# Plata2.net
KiCad netlist of a schematic drawn in EAGLE
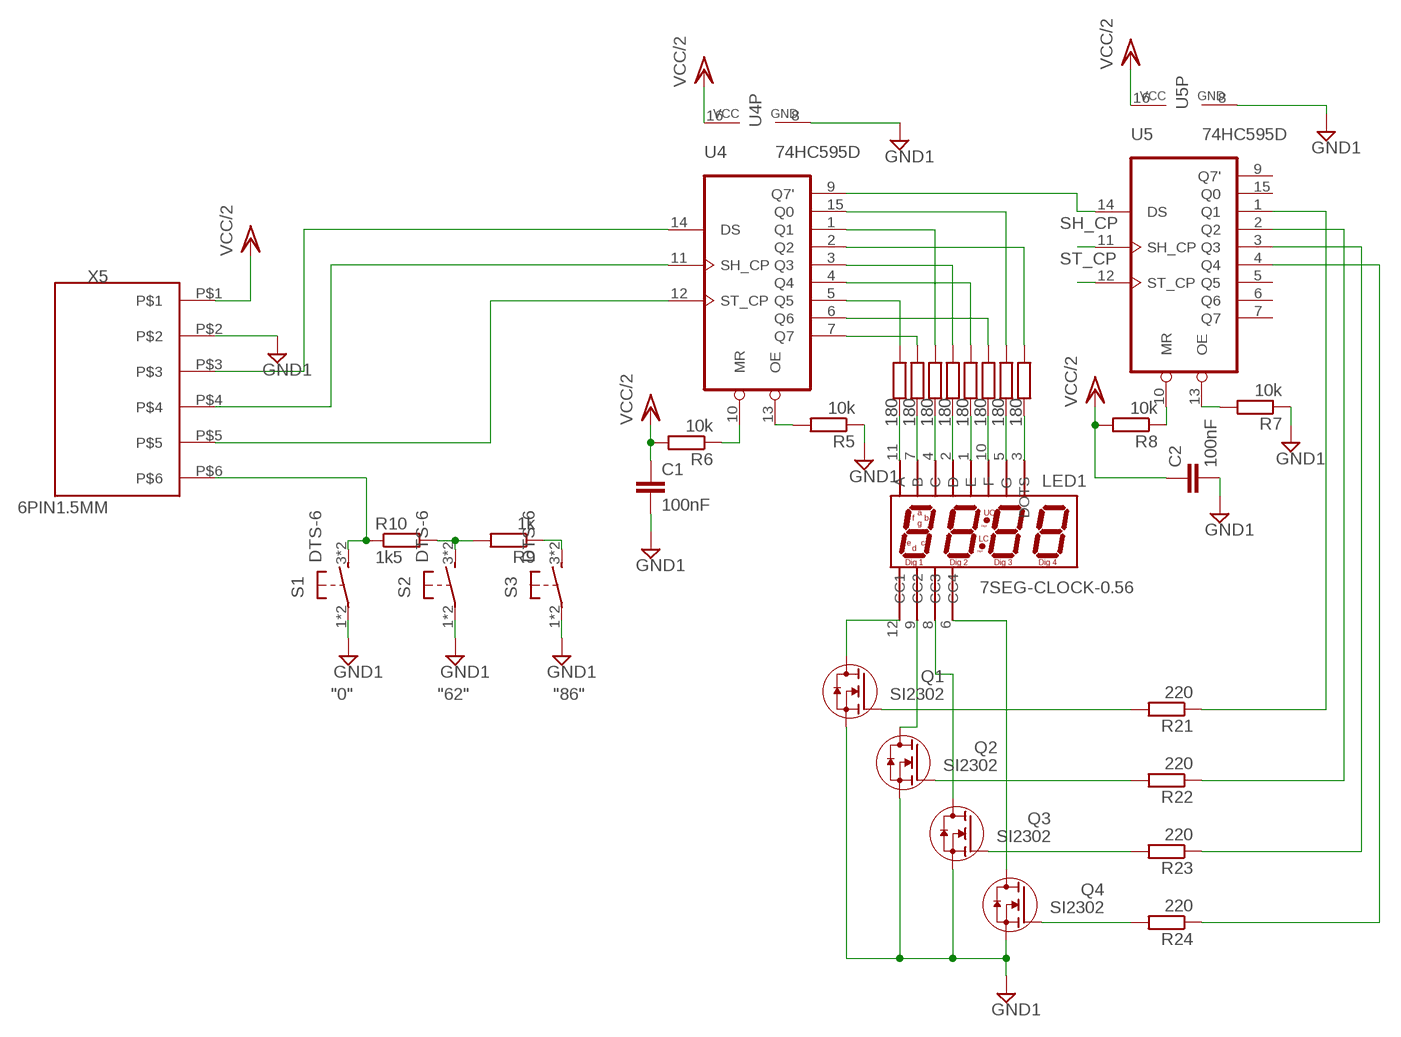
[diagram p0: schematic, sheet 1]

(export (version "E")
  (design (tool "Eeschema 10.0.6"))
  (components
    (comp (ref "C1")
      (value "100nF")
      (footprint "eagle-import:C0603")
      (libsource (lib "eagle-import") (part "C-EUC0603"))
    )
    (comp (ref "C2")
      (value "100nF")
      (footprint "eagle-import:C0603")
      (libsource (lib "eagle-import") (part "C-EUC0603"))
    )
    (comp (ref "LED1")
      (value "7SEG-CLOCK-0.56")
      (footprint "eagle-import:7SEG_4DIG_0.56")
      (libsource (lib "eagle-import") (part "7SEG-CLOCK-0.56"))
    )
    (comp (ref "Q1")
      (value "SI2302")
      (footprint "eagle-import:SOT-23-GSD")
      (libsource (lib "eagle-import") (part "SI2302"))
    )
    (comp (ref "Q2")
      (value "SI2302")
      (footprint "eagle-import:SOT-23-GSD")
      (libsource (lib "eagle-import") (part "SI2302"))
    )
    (comp (ref "Q3")
      (value "SI2302")
      (footprint "eagle-import:SOT-23-GSD")
      (libsource (lib "eagle-import") (part "SI2302"))
    )
    (comp (ref "Q4")
      (value "SI2302")
      (footprint "eagle-import:SOT-23-GSD")
      (libsource (lib "eagle-import") (part "SI2302"))
    )
    (comp (ref "R5")
      (value "10k")
      (footprint "eagle-import:R0805")
      (libsource (lib "eagle-import") (part "R-EU_R0805"))
    )
    (comp (ref "R6")
      (value "10k")
      (footprint "eagle-import:R0805")
      (libsource (lib "eagle-import") (part "R-EU_R0805"))
    )
    (comp (ref "R7")
      (value "10k")
      (footprint "eagle-import:R0805")
      (libsource (lib "eagle-import") (part "R-EU_R0805"))
    )
    (comp (ref "R8")
      (value "10k")
      (footprint "eagle-import:R0805")
      (libsource (lib "eagle-import") (part "R-EU_R0805"))
    )
    (comp (ref "R9")
      (value "1k")
      (footprint "eagle-import:R0805")
      (libsource (lib "eagle-import") (part "R-EU_R0805"))
    )
    (comp (ref "R10")
      (value "1k5")
      (footprint "eagle-import:R0805")
      (libsource (lib "eagle-import") (part "R-EU_R0805"))
    )
    (comp (ref "R17")
      (value "180")
      (footprint "eagle-import:R0805")
      (libsource (lib "eagle-import") (part "R-EU_R0805"))
    )
    (comp (ref "R18")
      (value "180")
      (footprint "eagle-import:R0805")
      (libsource (lib "eagle-import") (part "R-EU_R0805"))
    )
    (comp (ref "R19")
      (value "180")
      (footprint "eagle-import:R0805")
      (libsource (lib "eagle-import") (part "R-EU_R0805"))
    )
    (comp (ref "R20")
      (value "180")
      (footprint "eagle-import:R0805")
      (libsource (lib "eagle-import") (part "R-EU_R0805"))
    )
    (comp (ref "R21")
      (value "220")
      (footprint "eagle-import:R0805")
      (libsource (lib "eagle-import") (part "R-EU_R0805"))
    )
    (comp (ref "R22")
      (value "220")
      (footprint "eagle-import:R0805")
      (libsource (lib "eagle-import") (part "R-EU_R0805"))
    )
    (comp (ref "R23")
      (value "220")
      (footprint "eagle-import:R0805")
      (libsource (lib "eagle-import") (part "R-EU_R0805"))
    )
    (comp (ref "R24")
      (value "220")
      (footprint "eagle-import:R0805")
      (libsource (lib "eagle-import") (part "R-EU_R0805"))
    )
    (comp (ref "R25")
      (value "180")
      (footprint "eagle-import:R0805")
      (libsource (lib "eagle-import") (part "R-EU_R0805"))
    )
    (comp (ref "R26")
      (value "180")
      (footprint "eagle-import:R0805")
      (libsource (lib "eagle-import") (part "R-EU_R0805"))
    )
    (comp (ref "R27")
      (value "180")
      (footprint "eagle-import:R0805")
      (libsource (lib "eagle-import") (part "R-EU_R0805"))
    )
    (comp (ref "R28")
      (value "180")
      (footprint "eagle-import:R0805")
      (libsource (lib "eagle-import") (part "R-EU_R0805"))
    )
    (comp (ref "S1")
      (value "DTS-6")
      (footprint "eagle-import:DTS-6")
      (libsource (lib "eagle-import") (part "DTS-6"))
    )
    (comp (ref "S2")
      (value "DTS-6")
      (footprint "eagle-import:DTS-6")
      (libsource (lib "eagle-import") (part "DTS-6"))
    )
    (comp (ref "S3")
      (value "DTS-6")
      (footprint "eagle-import:DTS-6")
      (libsource (lib "eagle-import") (part "DTS-6"))
    )
    (comp (ref "U4")
      (value "74HC595D")
      (footprint "eagle-import:SO16")
      (libsource (lib "eagle-import") (part "74595DHC"))
    )
    (comp (ref "U5")
      (value "74HC595D")
      (footprint "eagle-import:SO16")
      (libsource (lib "eagle-import") (part "74595DHC"))
    )
    (comp (ref "X5")
      (value "6PIN1.5MM")
      (footprint "eagle-import:6PIN_1.5MM")
      (libsource (lib "eagle-import") (part "6PIN1.5MM"))
    )
  )
  (nets
    (net (code "1") (name "/SH_CP") (class "Default")
      (node (ref "U4") (pin "11") (pinfunction "SH_CP_11") (pintype "input"))
      (node (ref "U5") (pin "11") (pinfunction "SH_CP_11") (pintype "input"))
      (node (ref "X5") (pin "P$4") (pinfunction "P$4_P$4") (pintype "bidirectional"))
    )
    (net (code "2") (name "/ST_CP") (class "Default")
      (node (ref "U4") (pin "12") (pinfunction "ST_CP_12") (pintype "input"))
      (node (ref "U5") (pin "12") (pinfunction "ST_CP_12") (pintype "input"))
      (node (ref "X5") (pin "P$5") (pinfunction "P$5_P$5") (pintype "bidirectional"))
    )
    (net (code "3") (name "GND1") (class "Default")
      (node (ref "C1") (pin "2") (pinfunction "2_2") (pintype "passive"))
      (node (ref "C2") (pin "2") (pinfunction "2_2") (pintype "passive"))
      (node (ref "Q1") (pin "S") (pinfunction "S_S") (pintype "passive"))
      (node (ref "Q2") (pin "S") (pinfunction "S_S") (pintype "passive"))
      (node (ref "Q3") (pin "S") (pinfunction "S_S") (pintype "passive"))
      (node (ref "Q4") (pin "S") (pinfunction "S_S") (pintype "passive"))
      (node (ref "R5") (pin "1") (pinfunction "1_1") (pintype "passive"))
      (node (ref "R7") (pin "1") (pinfunction "1_1") (pintype "passive"))
      (node (ref "S1") (pin "1") (pinfunction "1_1") (pintype "passive"))
      (node (ref "S1") (pin "2") (pinfunction "1_2") (pintype "passive"))
      (node (ref "S2") (pin "1") (pinfunction "1_1") (pintype "passive"))
      (node (ref "S2") (pin "2") (pinfunction "1_2") (pintype "passive"))
      (node (ref "S3") (pin "1") (pinfunction "1_1") (pintype "passive"))
      (node (ref "S3") (pin "2") (pinfunction "1_2") (pintype "passive"))
      (node (ref "U4") (pin "8") (pinfunction "GND_8") (pintype "power_in"))
      (node (ref "U5") (pin "8") (pinfunction "GND_8") (pintype "power_in"))
      (node (ref "X5") (pin "P$2") (pinfunction "P$2_P$2") (pintype "bidirectional"))
    )
    (net (code "4") (name "Net-(LED1-A)") (class "Default")
      (node (ref "LED1") (pin "11") (pinfunction "A_11") (pintype "input"))
      (node (ref "R17") (pin "2") (pinfunction "2_2") (pintype "passive"))
    )
    (net (code "5") (name "Net-(LED1-B)") (class "Default")
      (node (ref "LED1") (pin "7") (pinfunction "B_7") (pintype "input"))
      (node (ref "R18") (pin "2") (pinfunction "2_2") (pintype "passive"))
    )
    (net (code "6") (name "Net-(LED1-C)") (class "Default")
      (node (ref "LED1") (pin "4") (pinfunction "C_4") (pintype "input"))
      (node (ref "R19") (pin "2") (pinfunction "2_2") (pintype "passive"))
    )
    (net (code "7") (name "Net-(LED1-CC1)") (class "Default")
      (node (ref "LED1") (pin "12") (pinfunction "CC1_12") (pintype "input"))
      (node (ref "Q1") (pin "D") (pinfunction "D_D") (pintype "passive"))
    )
    (net (code "8") (name "Net-(LED1-CC2)") (class "Default")
      (node (ref "LED1") (pin "9") (pinfunction "CC2_9") (pintype "input"))
      (node (ref "Q2") (pin "D") (pinfunction "D_D") (pintype "passive"))
    )
    (net (code "9") (name "Net-(LED1-CC3)") (class "Default")
      (node (ref "LED1") (pin "8") (pinfunction "CC3_8") (pintype "input"))
      (node (ref "Q3") (pin "D") (pinfunction "D_D") (pintype "passive"))
    )
    (net (code "10") (name "Net-(LED1-CC4)") (class "Default")
      (node (ref "LED1") (pin "6") (pinfunction "CC4_6") (pintype "input"))
      (node (ref "Q4") (pin "D") (pinfunction "D_D") (pintype "passive"))
    )
    (net (code "11") (name "Net-(LED1-D)") (class "Default")
      (node (ref "LED1") (pin "2") (pinfunction "D_2") (pintype "input"))
      (node (ref "R20") (pin "2") (pinfunction "2_2") (pintype "passive"))
    )
    (net (code "12") (name "Net-(LED1-DOTS)") (class "Default")
      (node (ref "LED1") (pin "3") (pinfunction "DOTS_3") (pintype "input"))
      (node (ref "R28") (pin "2") (pinfunction "2_2") (pintype "passive"))
    )
    (net (code "13") (name "Net-(LED1-E)") (class "Default")
      (node (ref "LED1") (pin "1") (pinfunction "E_1") (pintype "input"))
      (node (ref "R25") (pin "2") (pinfunction "2_2") (pintype "passive"))
    )
    (net (code "14") (name "Net-(LED1-F)") (class "Default")
      (node (ref "LED1") (pin "10") (pinfunction "F_10") (pintype "input"))
      (node (ref "R26") (pin "2") (pinfunction "2_2") (pintype "passive"))
    )
    (net (code "15") (name "Net-(LED1-G)") (class "Default")
      (node (ref "LED1") (pin "5") (pinfunction "G_5") (pintype "input"))
      (node (ref "R27") (pin "2") (pinfunction "2_2") (pintype "passive"))
    )
    (net (code "16") (name "Net-(Q1-PadG)") (class "Default")
      (node (ref "Q1") (pin "G") (pinfunction "G_G") (pintype "passive"))
      (node (ref "R21") (pin "2") (pinfunction "2_2") (pintype "passive"))
    )
    (net (code "17") (name "Net-(Q2-PadG)") (class "Default")
      (node (ref "Q2") (pin "G") (pinfunction "G_G") (pintype "passive"))
      (node (ref "R22") (pin "2") (pinfunction "2_2") (pintype "passive"))
    )
    (net (code "18") (name "Net-(Q3-PadG)") (class "Default")
      (node (ref "Q3") (pin "G") (pinfunction "G_G") (pintype "passive"))
      (node (ref "R23") (pin "2") (pinfunction "2_2") (pintype "passive"))
    )
    (net (code "19") (name "Net-(Q4-PadG)") (class "Default")
      (node (ref "Q4") (pin "G") (pinfunction "G_G") (pintype "passive"))
      (node (ref "R24") (pin "2") (pinfunction "2_2") (pintype "passive"))
    )
    (net (code "20") (name "Net-(R9-Pad1)") (class "Default")
      (node (ref "R9") (pin "1") (pinfunction "1_1") (pintype "passive"))
      (node (ref "S3") (pin "3") (pinfunction "2_3") (pintype "passive"))
      (node (ref "S3") (pin "4") (pinfunction "2_4") (pintype "passive"))
    )
    (net (code "21") (name "Net-(R10-Pad1)") (class "Default")
      (node (ref "R10") (pin "1") (pinfunction "1_1") (pintype "passive"))
      (node (ref "S1") (pin "3") (pinfunction "2_3") (pintype "passive"))
      (node (ref "S1") (pin "4") (pinfunction "2_4") (pintype "passive"))
      (node (ref "X5") (pin "P$6") (pinfunction "P$6_P$6") (pintype "bidirectional"))
    )
    (net (code "22") (name "Net-(R10-Pad2)") (class "Default")
      (node (ref "R10") (pin "2") (pinfunction "2_2") (pintype "passive"))
      (node (ref "R9") (pin "2") (pinfunction "2_2") (pintype "passive"))
      (node (ref "S2") (pin "3") (pinfunction "2_3") (pintype "passive"))
      (node (ref "S2") (pin "4") (pinfunction "2_4") (pintype "passive"))
    )
    (net (code "23") (name "Net-(U4A-DS)") (class "Default")
      (node (ref "U4") (pin "14") (pinfunction "DS_14") (pintype "input"))
      (node (ref "X5") (pin "P$3") (pinfunction "P$3_P$3") (pintype "bidirectional"))
    )
    (net (code "24") (name "Net-(U4A-MR)") (class "Default")
      (node (ref "R6") (pin "1") (pinfunction "1_1") (pintype "passive"))
      (node (ref "U4") (pin "10") (pinfunction "MR_10") (pintype "input"))
    )
    (net (code "25") (name "Net-(U4A-OE)") (class "Default")
      (node (ref "R5") (pin "2") (pinfunction "2_2") (pintype "passive"))
      (node (ref "U4") (pin "13") (pinfunction "OE_13") (pintype "input"))
    )
    (net (code "26") (name "Net-(U4A-Q0)") (class "Default")
      (node (ref "R27") (pin "1") (pinfunction "1_1") (pintype "passive"))
      (node (ref "U4") (pin "15") (pinfunction "Q0_15") (pintype "output"))
    )
    (net (code "27") (name "Net-(U4A-Q1)") (class "Default")
      (node (ref "R19") (pin "1") (pinfunction "1_1") (pintype "passive"))
      (node (ref "U4") (pin "1") (pinfunction "Q1_1") (pintype "output"))
    )
    (net (code "28") (name "Net-(U4A-Q2)") (class "Default")
      (node (ref "R28") (pin "1") (pinfunction "1_1") (pintype "passive"))
      (node (ref "U4") (pin "2") (pinfunction "Q2_2") (pintype "output"))
    )
    (net (code "29") (name "Net-(U4A-Q3)") (class "Default")
      (node (ref "R20") (pin "1") (pinfunction "1_1") (pintype "passive"))
      (node (ref "U4") (pin "3") (pinfunction "Q3_3") (pintype "output"))
    )
    (net (code "30") (name "Net-(U4A-Q4)") (class "Default")
      (node (ref "R25") (pin "1") (pinfunction "1_1") (pintype "passive"))
      (node (ref "U4") (pin "4") (pinfunction "Q4_4") (pintype "output"))
    )
    (net (code "31") (name "Net-(U4A-Q5)") (class "Default")
      (node (ref "R17") (pin "1") (pinfunction "1_1") (pintype "passive"))
      (node (ref "U4") (pin "5") (pinfunction "Q5_5") (pintype "output"))
    )
    (net (code "32") (name "Net-(U4A-Q6)") (class "Default")
      (node (ref "R26") (pin "1") (pinfunction "1_1") (pintype "passive"))
      (node (ref "U4") (pin "6") (pinfunction "Q6_6") (pintype "output"))
    )
    (net (code "33") (name "Net-(U4A-Q7')") (class "Default")
      (node (ref "U4") (pin "9") (pinfunction "Q7'_9") (pintype "output"))
      (node (ref "U5") (pin "14") (pinfunction "DS_14") (pintype "input"))
    )
    (net (code "34") (name "Net-(U4A-Q7)") (class "Default")
      (node (ref "R18") (pin "1") (pinfunction "1_1") (pintype "passive"))
      (node (ref "U4") (pin "7") (pinfunction "Q7_7") (pintype "output"))
    )
    (net (code "35") (name "Net-(U5A-MR)") (class "Default")
      (node (ref "R8") (pin "1") (pinfunction "1_1") (pintype "passive"))
      (node (ref "U5") (pin "10") (pinfunction "MR_10") (pintype "input"))
    )
    (net (code "36") (name "Net-(U5A-OE)") (class "Default")
      (node (ref "R7") (pin "2") (pinfunction "2_2") (pintype "passive"))
      (node (ref "U5") (pin "13") (pinfunction "OE_13") (pintype "input"))
    )
    (net (code "37") (name "Net-(U5A-Q1)") (class "Default")
      (node (ref "R21") (pin "1") (pinfunction "1_1") (pintype "passive"))
      (node (ref "U5") (pin "1") (pinfunction "Q1_1") (pintype "output"))
    )
    (net (code "38") (name "Net-(U5A-Q2)") (class "Default")
      (node (ref "R22") (pin "1") (pinfunction "1_1") (pintype "passive"))
      (node (ref "U5") (pin "2") (pinfunction "Q2_2") (pintype "output"))
    )
    (net (code "39") (name "Net-(U5A-Q3)") (class "Default")
      (node (ref "R23") (pin "1") (pinfunction "1_1") (pintype "passive"))
      (node (ref "U5") (pin "3") (pinfunction "Q3_3") (pintype "output"))
    )
    (net (code "40") (name "Net-(U5A-Q4)") (class "Default")
      (node (ref "R24") (pin "1") (pinfunction "1_1") (pintype "passive"))
      (node (ref "U5") (pin "4") (pinfunction "Q4_4") (pintype "output"))
    )
    (net (code "41") (name "VCC{slash}2") (class "Default")
      (node (ref "C1") (pin "1") (pinfunction "1_1") (pintype "passive"))
      (node (ref "C2") (pin "1") (pinfunction "1_1") (pintype "passive"))
      (node (ref "R6") (pin "2") (pinfunction "2_2") (pintype "passive"))
      (node (ref "R8") (pin "2") (pinfunction "2_2") (pintype "passive"))
      (node (ref "U4") (pin "16") (pinfunction "VCC_16") (pintype "power_in"))
      (node (ref "U5") (pin "16") (pinfunction "VCC_16") (pintype "power_in"))
      (node (ref "X5") (pin "P$1") (pinfunction "P$1_P$1") (pintype "bidirectional"))
    )
    (net (code "42") (name "unconnected-(U5A-Q0-Pad15)") (class "Default")
      (node (ref "U5") (pin "15") (pinfunction "Q0_15") (pintype "output"))
    )
    (net (code "43") (name "unconnected-(U5A-Q5-Pad5)") (class "Default")
      (node (ref "U5") (pin "5") (pinfunction "Q5_5") (pintype "output"))
    )
    (net (code "44") (name "unconnected-(U5A-Q6-Pad6)") (class "Default")
      (node (ref "U5") (pin "6") (pinfunction "Q6_6") (pintype "output"))
    )
    (net (code "45") (name "unconnected-(U5A-Q7'-Pad9)") (class "Default")
      (node (ref "U5") (pin "9") (pinfunction "Q7'_9") (pintype "output"))
    )
    (net (code "46") (name "unconnected-(U5A-Q7-Pad7)") (class "Default")
      (node (ref "U5") (pin "7") (pinfunction "Q7_7") (pintype "output"))
    )
  )
)
